# MainBoard_MCU_Power.net
KiCad netlist of a schematic drawn in Altium Designer
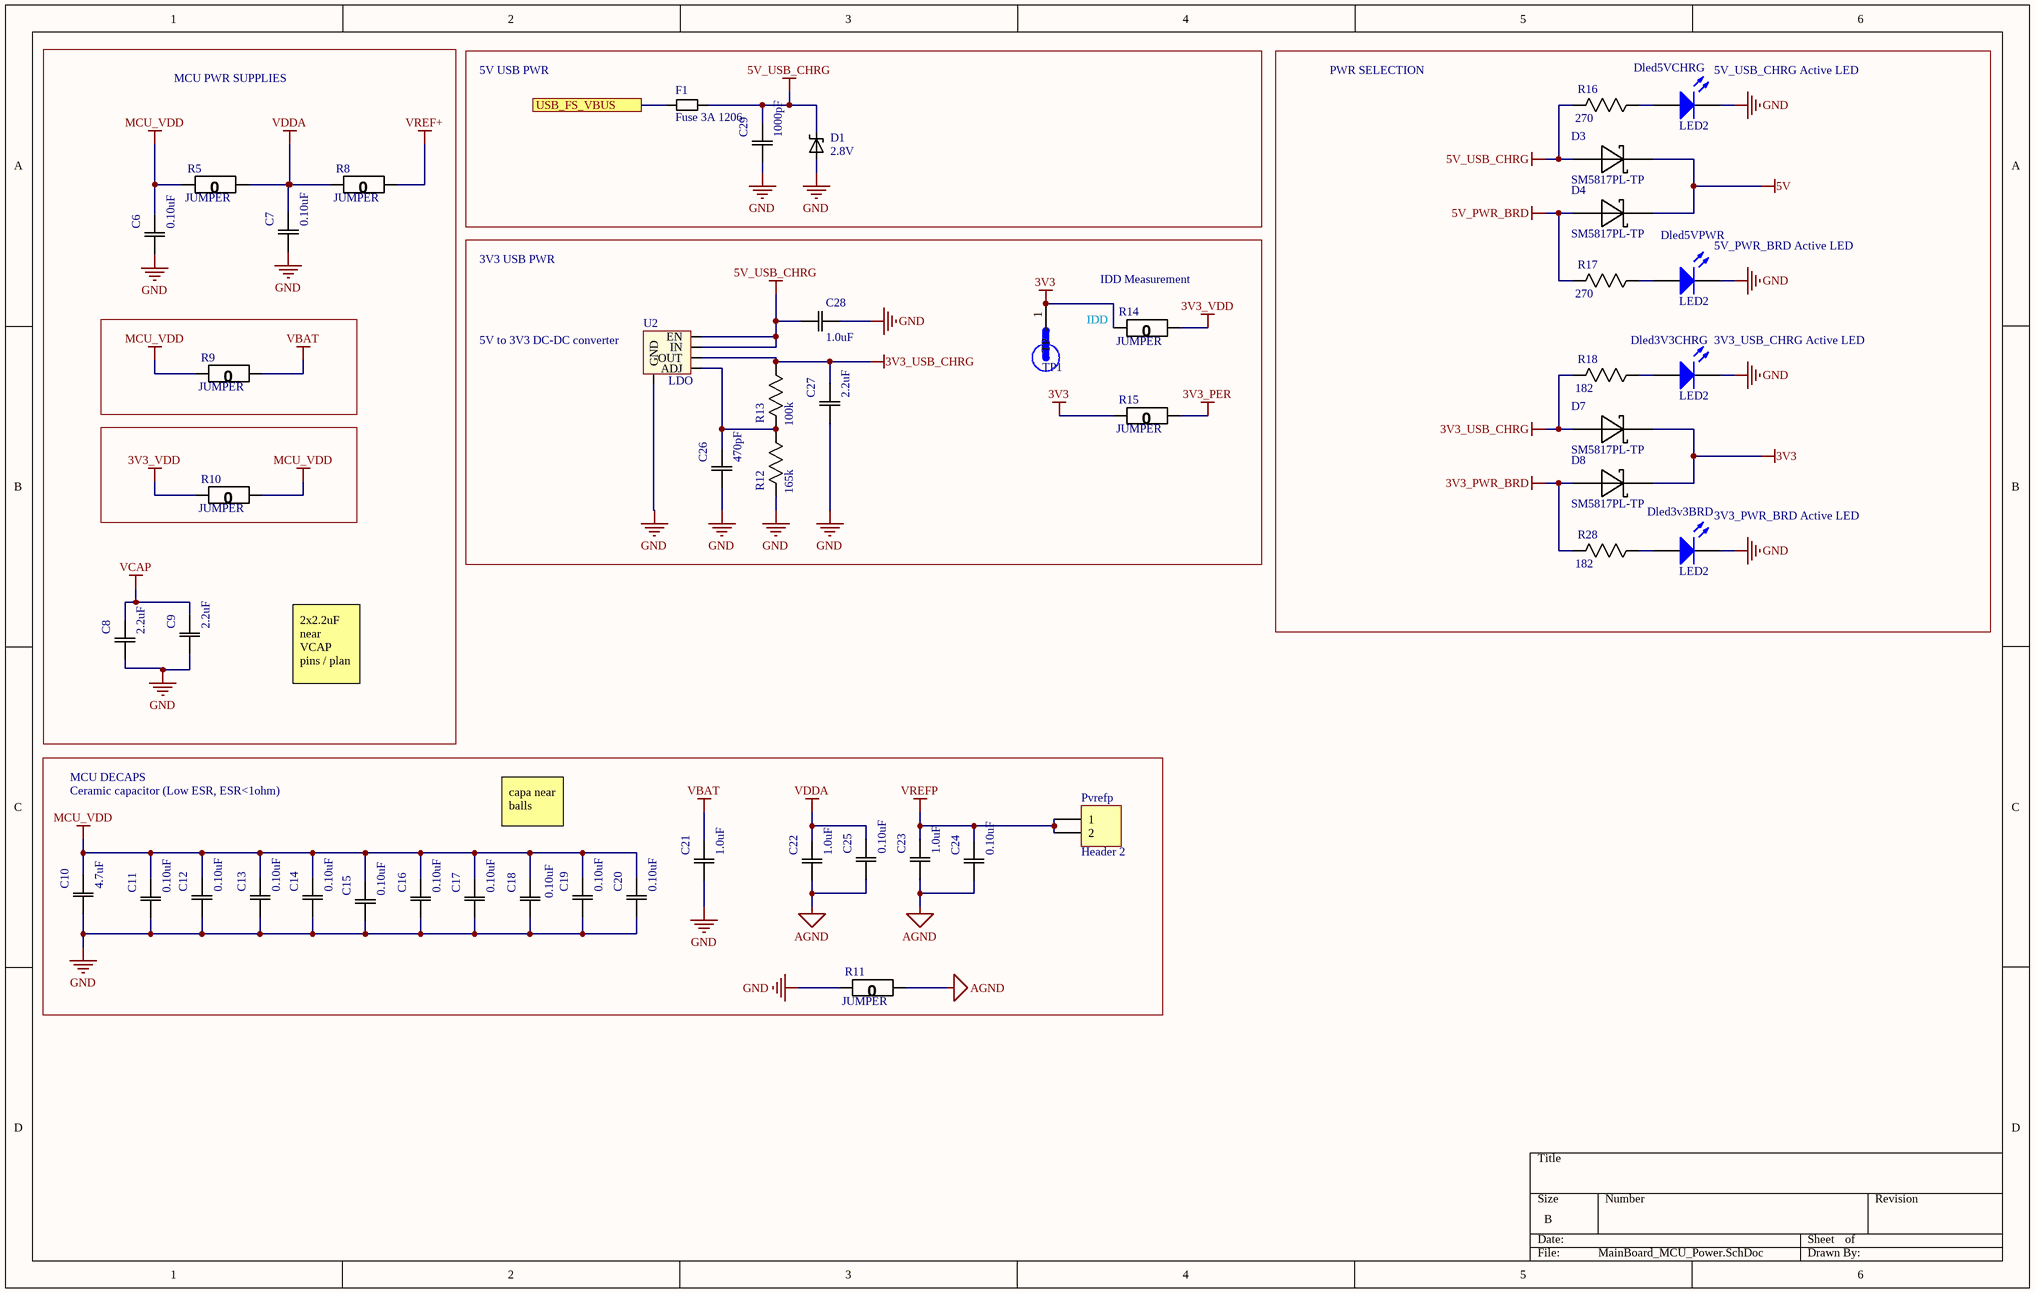
[diagram p0: MainBoard_MCU_Power.SchDoc]

(export (version "E")
  (design (tool "Eeschema 10.0.6"))
  (components
    (comp (ref "C6")
      (value "0.10uF")
      (footprint "0603")
      (description "CAP CER 0.10UF 16V X5R 0603/0805")
      (fields (field (name "TOLERANCE") "10%"))
      (libsource (lib "AltiumLibraries") (part "CAP 0.10uF 16V"))
    )
    (comp (ref "C7")
      (value "0.10uF")
      (footprint "0603")
      (description "CAP CER 0.10UF 16V X5R 0603/0805")
      (fields (field (name "TOLERANCE") "10%"))
      (libsource (lib "AltiumLibraries") (part "CAP 0.10uF 16V"))
    )
    (comp (ref "C8")
      (value "2.2uF")
      (footprint "0603")
      (description "CAP CER 2.2UF 16V X5R 0603/0805")
      (fields (field (name "TOLERANCE") "10%"))
      (libsource (lib "AltiumLibraries") (part "CAP 2.2uF 16V"))
    )
    (comp (ref "C9")
      (value "2.2uF")
      (footprint "0603")
      (description "CAP CER 2.2UF 16V X5R 0603/0805")
      (fields (field (name "TOLERANCE") "10%"))
      (libsource (lib "AltiumLibraries") (part "CAP 2.2uF 16V"))
    )
    (comp (ref "C10")
      (value "4.7uF")
      (footprint "0603")
      (description "CAP CER 4.7UF 16V X5R 0603/0805")
      (fields (field (name "TOLERANCE") "10%"))
      (libsource (lib "AltiumLibraries") (part "CAP 4.7uF 16V"))
    )
    (comp (ref "C11")
      (value "0.10uF")
      (footprint "0603")
      (description "CAP CER 0.10UF 16V X5R 0603/0805")
      (fields (field (name "TOLERANCE") "10%"))
      (libsource (lib "AltiumLibraries") (part "CAP 0.10uF 16V"))
    )
    (comp (ref "C12")
      (value "0.10uF")
      (footprint "0603")
      (description "CAP CER 0.10UF 16V X5R 0603/0805")
      (fields (field (name "TOLERANCE") "10%"))
      (libsource (lib "AltiumLibraries") (part "CAP 0.10uF 16V"))
    )
    (comp (ref "C13")
      (value "0.10uF")
      (footprint "0603")
      (description "CAP CER 0.10UF 16V X5R 0603/0805")
      (fields (field (name "TOLERANCE") "10%"))
      (libsource (lib "AltiumLibraries") (part "CAP 0.10uF 16V"))
    )
    (comp (ref "C14")
      (value "0.10uF")
      (footprint "0603")
      (description "CAP CER 0.10UF 16V X5R 0603/0805")
      (fields (field (name "TOLERANCE") "10%"))
      (libsource (lib "AltiumLibraries") (part "CAP 0.10uF 16V"))
    )
    (comp (ref "C15")
      (value "0.10uF")
      (footprint "0603")
      (description "CAP CER 0.10UF 16V X5R 0603/0805")
      (fields (field (name "TOLERANCE") "10%"))
      (libsource (lib "AltiumLibraries") (part "CAP 0.10uF 16V"))
    )
    (comp (ref "C16")
      (value "0.10uF")
      (footprint "0603")
      (description "CAP CER 0.10UF 16V X5R 0603/0805")
      (fields (field (name "TOLERANCE") "10%"))
      (libsource (lib "AltiumLibraries") (part "CAP 0.10uF 16V"))
    )
    (comp (ref "C17")
      (value "0.10uF")
      (footprint "0603")
      (description "CAP CER 0.10UF 16V X5R 0603/0805")
      (fields (field (name "TOLERANCE") "10%"))
      (libsource (lib "AltiumLibraries") (part "CAP 0.10uF 16V"))
    )
    (comp (ref "C18")
      (value "0.10uF")
      (footprint "0603")
      (description "CAP CER 0.10UF 16V X5R 0603/0805")
      (fields (field (name "TOLERANCE") "10%"))
      (libsource (lib "AltiumLibraries") (part "CAP 0.10uF 16V"))
    )
    (comp (ref "C19")
      (value "0.10uF")
      (footprint "0603")
      (description "CAP CER 0.10UF 16V X5R 0603/0805")
      (fields (field (name "TOLERANCE") "10%"))
      (libsource (lib "AltiumLibraries") (part "CAP 0.10uF 16V"))
    )
    (comp (ref "C20")
      (value "0.10uF")
      (footprint "0603")
      (description "CAP CER 0.10UF 16V X5R 0603/0805")
      (fields (field (name "TOLERANCE") "10%"))
      (libsource (lib "AltiumLibraries") (part "CAP 0.10uF 16V"))
    )
    (comp (ref "C21")
      (value "1.0uF")
      (footprint "0603")
      (description "CAP CER 1.0UF 16V X5R 0603/0805")
      (fields (field (name "TOLERANCE") "10%"))
      (libsource (lib "AltiumLibraries") (part "CAP 1.0uF 16V"))
    )
    (comp (ref "C22")
      (value "1.0uF")
      (footprint "0603")
      (description "CAP CER 1.0UF 16V X5R 0603/0805")
      (fields (field (name "TOLERANCE") "10%"))
      (libsource (lib "AltiumLibraries") (part "CAP 1.0uF 16V"))
    )
    (comp (ref "C23")
      (value "1.0uF")
      (footprint "0603")
      (description "CAP CER 1.0UF 16V X5R 0603/0805")
      (fields (field (name "TOLERANCE") "10%"))
      (libsource (lib "AltiumLibraries") (part "CAP 1.0uF 16V"))
    )
    (comp (ref "C24")
      (value "0.10uF")
      (footprint "0603")
      (description "CAP CER 0.10UF 16V X5R 0603/0805")
      (fields (field (name "TOLERANCE") "10%"))
      (libsource (lib "AltiumLibraries") (part "CAP 0.10uF 16V"))
    )
    (comp (ref "C25")
      (value "0.10uF")
      (footprint "0603")
      (description "CAP CER 0.10UF 16V X5R 0603/0805")
      (fields (field (name "TOLERANCE") "10%"))
      (libsource (lib "AltiumLibraries") (part "CAP 0.10uF 16V"))
    )
    (comp (ref "C26")
      (value "470pF")
      (footprint "0603")
      (description "CAP CER 470PF 16V X5R 0603/0805")
      (fields (field (name "TOLERANCE") "10%"))
      (libsource (lib "AltiumLibraries") (part "CAP 470pF 16V"))
    )
    (comp (ref "C27")
      (value "2.2uF")
      (footprint "0603")
      (description "CAP CER 2.2UF 16V X5R 0603/0805")
      (fields (field (name "TOLERANCE") "10%"))
      (libsource (lib "") (part "CAP 2.2uF 16V_1"))
    )
    (comp (ref "C28")
      (value "1.0uF")
      (footprint "0603")
      (description "CAP CER 1.0UF 16V X5R 0603/0805")
      (fields (field (name "TOLERANCE") "10%"))
      (libsource (lib "AltiumLibraries") (part "CAP 1.0uF 16V"))
    )
    (comp (ref "C29")
      (value "1000pF")
      (footprint "0603")
      (description "CAP CER 1000PF 16V X5R 0603/0805")
      (fields (field (name "TOLERANCE") "10%"))
      (libsource (lib "AltiumLibraries") (part "CAP 1000pF 16V"))
    )
    (comp (ref "D1")
      (value "2.8V")
      (footprint "SOD-123")
      (description "Zener Diode 2.8V 500mW ±5% Surface Mount SOD-123")
      (libsource (lib "AltiumLibraries") (part "DIODE ZENER 2.8V 500mW"))
    )
    (comp (ref "D3")
      (value "SM5817PL-TP")
      (footprint "SOD-123")
      (description "Diode Schottky 20V 1A Surface Mount SOD-123FL")
      (fields (field (name "MF") "Micro Commercial Co"))
      (libsource (lib "AltiumLibraries") (part "DIODE SCHOTTKY 20V 1A"))
    )
    (comp (ref "D4")
      (value "SM5817PL-TP")
      (footprint "SOD-123")
      (description "Diode Schottky 20V 1A Surface Mount SOD-123FL")
      (fields (field (name "MF") "Micro Commercial Co"))
      (libsource (lib "AltiumLibraries") (part "DIODE SCHOTTKY 20V 1A"))
    )
    (comp (ref "D7")
      (value "SM5817PL-TP")
      (footprint "SOD-123")
      (description "Diode Schottky 20V 1A Surface Mount SOD-123FL")
      (fields (field (name "MF") "Micro Commercial Co"))
      (libsource (lib "AltiumLibraries") (part "DIODE SCHOTTKY 20V 1A"))
    )
    (comp (ref "D8")
      (value "SM5817PL-TP")
      (footprint "SOD-123")
      (description "Diode Schottky 20V 1A Surface Mount SOD-123FL")
      (fields (field (name "MF") "Micro Commercial Co"))
      (libsource (lib "AltiumLibraries") (part "DIODE SCHOTTKY 20V 1A"))
    )
    (comp (ref "Dled3v3BRD")
      (value "LED2")
      (footprint "3.2X1.6X1.1")
      (description "Typical RED, GREEN, YELLOW, AMBER GaAs LED")
      (libsource (lib "AltiumLibraries") (part "LED GREEN SMD"))
    )
    (comp (ref "Dled3V3CHRG")
      (value "LED2")
      (footprint "3.2X1.6X1.1")
      (description "Typical RED, GREEN, YELLOW, AMBER GaAs LED")
      (libsource (lib "AltiumLibraries") (part "LED GREEN SMD"))
    )
    (comp (ref "Dled5VCHRG")
      (value "LED2")
      (footprint "3.2X1.6X1.1")
      (description "Typical RED, GREEN, YELLOW, AMBER GaAs LED")
      (libsource (lib "AltiumLibraries") (part "LED GREEN SMD"))
    )
    (comp (ref "Dled5VPWR")
      (value "LED2")
      (footprint "3.2X1.6X1.1")
      (description "Typical RED, GREEN, YELLOW, AMBER GaAs LED")
      (libsource (lib "AltiumLibraries") (part "LED GREEN SMD"))
    )
    (comp (ref "F1")
      (value "Fuse 3A 1206")
      (footprint "1206")
      (description "FUSE 3A 63V AC/DC SLOW 1206")
      (libsource (lib "AltiumLibraries") (part "FUSE 3A 63V SLOW"))
    )
    (comp (ref "Pvrefp")
      (value "Header 2")
      (footprint "HDR1X2")
      (description "Header, 2-Pin")
      (fields (field (name "PUBLISHER") "Altium Limited"))
      (libsource (lib "Miscellaneous Connectors") (part "Header 2"))
    )
    (comp (ref "R5")
      (value "JUMPER")
      (footprint "0805")
      (description "RES SMD 0 OHM JUMPER GENERIC 0805")
      (libsource (lib "AltiumLibraries") (part "RES 0 JUMPER"))
    )
    (comp (ref "R8")
      (value "JUMPER")
      (footprint "0805")
      (description "RES SMD 0 OHM JUMPER GENERIC 0805")
      (libsource (lib "AltiumLibraries") (part "RES 0 JUMPER"))
    )
    (comp (ref "R9")
      (value "JUMPER")
      (footprint "0805")
      (description "RES SMD 0 OHM JUMPER GENERIC 0805")
      (libsource (lib "AltiumLibraries") (part "RES 0 JUMPER"))
    )
    (comp (ref "R10")
      (value "JUMPER")
      (footprint "0805")
      (description "RES SMD 0 OHM JUMPER GENERIC 0805")
      (libsource (lib "AltiumLibraries") (part "RES 0 JUMPER"))
    )
    (comp (ref "R11")
      (value "JUMPER")
      (footprint "0805")
      (description "RES SMD 0 OHM JUMPER GENERIC 0805")
      (libsource (lib "AltiumLibraries") (part "RES 0 JUMPER"))
    )
    (comp (ref "R12")
      (value "165k")
      (footprint "0805")
      (description "RES SMD 165K OHM 1% 1/4W 0805")
      (fields (field (name "TOLERANCE") "1%"))
      (libsource (lib "AltiumLibraries") (part "RES 165k 1/4W"))
    )
    (comp (ref "R13")
      (value "100k")
      (footprint "0805")
      (description "RES SMD 100K OHM 1% 1/8W 0805")
      (fields (field (name "TOLERANCE") "1%"))
      (libsource (lib "AltiumLibraries") (part "RES 100k 1/8W - 1%"))
    )
    (comp (ref "R14")
      (value "JUMPER")
      (footprint "0805")
      (description "RES SMD 0 OHM JUMPER GENERIC 0805")
      (libsource (lib "AltiumLibraries") (part "RES 0 JUMPER"))
    )
    (comp (ref "R15")
      (value "JUMPER")
      (footprint "0805")
      (description "RES SMD 0 OHM JUMPER GENERIC 0805")
      (libsource (lib "AltiumLibraries") (part "RES 0 JUMPER"))
    )
    (comp (ref "R16")
      (value "270")
      (footprint "0805")
      (description "RES SMD 270 OHM 5% 1/8W 0805")
      (fields (field (name "TOLERANCE") "5%"))
      (libsource (lib "AltiumLibraries") (part "RES 270.0 1/8W"))
    )
    (comp (ref "R17")
      (value "270")
      (footprint "0805")
      (description "RES SMD 270 OHM 5% 1/8W 0805")
      (fields (field (name "TOLERANCE") "5%"))
      (libsource (lib "AltiumLibraries") (part "RES 270.0 1/8W"))
    )
    (comp (ref "R18")
      (value "182")
      (footprint "0805")
      (description "RES SMD 182 OHM 1% 1/8W 0805")
      (fields (field (name "TOLERANCE") "1%"))
      (libsource (lib "AltiumLibraries") (part "RES 182.0 1/8W"))
    )
    (comp (ref "R28")
      (value "182")
      (footprint "0805")
      (description "RES SMD 182 OHM 1% 1/8W 0805")
      (fields (field (name "TOLERANCE") "1%"))
      (libsource (lib "AltiumLibraries") (part "RES 182.0 1/8W"))
    )
    (comp (ref "TP1")
      (value "Test Point - 5019")
      (footprint "TP380X203")
      (description "PC Test Point, Miniature Phosphor Bronze, Silver Plating Surface Mount Mounting Type")
      (fields (field (name "MP") "5019") (field (name "MF") "Keystone Electronics"))
      (libsource (lib "AltiumLibraries") (part "Test Point - 5019"))
    )
    (comp (ref "U2")
      (value "LDO")
      (footprint "REG LIN POS ADJ 500MA 8SOIC")
      (description "Linear Voltage Regulator IC  1 Output  500mA 8-SOIC")
      (fields (field (name "MF") "Texas Instruments") (field (name "MP") "TL5209DR"))
      (libsource (lib "AltiumLibraries") (part "REG LIN POS ADJ"))
    )
  )
  (nets
    (net (code "1") (name "/USB_FS_VBUS") (class "Default")
      (node (ref "F1") (pin "1") (pinfunction "1_1") (pintype "passive"))
    )
    (net (code "2") (name "3V3") (class "Default")
      (node (ref "D7") (pin "C") (pinfunction "K_C") (pintype "passive"))
      (node (ref "D8") (pin "C") (pinfunction "K_C") (pintype "passive"))
      (node (ref "R14") (pin "2") (pinfunction "R2_2") (pintype "passive"))
      (node (ref "R15") (pin "2") (pinfunction "R2_2") (pintype "passive"))
      (node (ref "TP1") (pin "1") (pinfunction "TP_1") (pintype "passive"))
    )
    (net (code "3") (name "3V3_PER") (class "Default")
      (node (ref "R15") (pin "1") (pinfunction "R1_1") (pintype "passive"))
    )
    (net (code "4") (name "3V3_PWR_BRD") (class "Default")
      (node (ref "D8") (pin "A") (pinfunction "A_A") (pintype "passive"))
      (node (ref "R28") (pin "2") (pinfunction "R2_2") (pintype "passive"))
    )
    (net (code "5") (name "3V3_USB_CHRG") (class "Default")
      (node (ref "C27") (pin "2") (pinfunction "C2_2") (pintype "passive"))
      (node (ref "D7") (pin "A") (pinfunction "A_A") (pintype "passive"))
      (node (ref "R13") (pin "1") (pinfunction "R1_1") (pintype "passive"))
      (node (ref "R18") (pin "2") (pinfunction "R2_2") (pintype "passive"))
      (node (ref "U2") (pin "OUT") (pinfunction "OUT_OUT") (pintype "passive"))
    )
    (net (code "6") (name "3V3_VDD") (class "Default")
      (node (ref "R10") (pin "2") (pinfunction "R2_2") (pintype "passive"))
      (node (ref "R14") (pin "1") (pinfunction "R1_1") (pintype "passive"))
    )
    (net (code "7") (name "5V") (class "Default")
      (node (ref "D3") (pin "C") (pinfunction "K_C") (pintype "passive"))
      (node (ref "D4") (pin "C") (pinfunction "K_C") (pintype "passive"))
    )
    (net (code "8") (name "5V_PWR_BRD") (class "Default")
      (node (ref "D4") (pin "A") (pinfunction "A_A") (pintype "passive"))
      (node (ref "R17") (pin "2") (pinfunction "R2_2") (pintype "passive"))
    )
    (net (code "9") (name "5V_USB_CHRG") (class "Default")
      (node (ref "C28") (pin "1") (pinfunction "C1_1") (pintype "passive"))
      (node (ref "C29") (pin "2") (pinfunction "C2_2") (pintype "passive"))
      (node (ref "D1") (pin "C") (pinfunction "C_C") (pintype "passive"))
      (node (ref "D3") (pin "A") (pinfunction "A_A") (pintype "passive"))
      (node (ref "F1") (pin "2") (pinfunction "2_2") (pintype "passive"))
      (node (ref "R16") (pin "2") (pinfunction "R2_2") (pintype "passive"))
      (node (ref "U2") (pin "EN") (pinfunction "EN_EN") (pintype "passive"))
      (node (ref "U2") (pin "IN") (pinfunction "IN_IN") (pintype "passive"))
    )
    (net (code "10") (name "AGND") (class "Default")
      (node (ref "C22") (pin "1") (pinfunction "C1_1") (pintype "passive"))
      (node (ref "C23") (pin "1") (pinfunction "C1_1") (pintype "passive"))
      (node (ref "C24") (pin "1") (pinfunction "C1_1") (pintype "passive"))
      (node (ref "C25") (pin "1") (pinfunction "C1_1") (pintype "passive"))
      (node (ref "R11") (pin "1") (pinfunction "R1_1") (pintype "passive"))
    )
    (net (code "11") (name "GND") (class "Default")
      (node (ref "C10") (pin "1") (pinfunction "C1_1") (pintype "passive"))
      (node (ref "C11") (pin "1") (pinfunction "C1_1") (pintype "passive"))
      (node (ref "C12") (pin "1") (pinfunction "C1_1") (pintype "passive"))
      (node (ref "C13") (pin "1") (pinfunction "C1_1") (pintype "passive"))
      (node (ref "C14") (pin "1") (pinfunction "C1_1") (pintype "passive"))
      (node (ref "C15") (pin "1") (pinfunction "C1_1") (pintype "passive"))
      (node (ref "C16") (pin "1") (pinfunction "C1_1") (pintype "passive"))
      (node (ref "C17") (pin "1") (pinfunction "C1_1") (pintype "passive"))
      (node (ref "C18") (pin "1") (pinfunction "C1_1") (pintype "passive"))
      (node (ref "C19") (pin "1") (pinfunction "C1_1") (pintype "passive"))
      (node (ref "C20") (pin "1") (pinfunction "C1_1") (pintype "passive"))
      (node (ref "C21") (pin "1") (pinfunction "C1_1") (pintype "passive"))
      (node (ref "C26") (pin "1") (pinfunction "C1_1") (pintype "passive"))
      (node (ref "C27") (pin "1") (pinfunction "C1_1") (pintype "passive"))
      (node (ref "C28") (pin "2") (pinfunction "C2_2") (pintype "passive"))
      (node (ref "C29") (pin "1") (pinfunction "C1_1") (pintype "passive"))
      (node (ref "C6") (pin "1") (pinfunction "C1_1") (pintype "passive"))
      (node (ref "C7") (pin "1") (pinfunction "C1_1") (pintype "passive"))
      (node (ref "C8") (pin "1") (pinfunction "C1_1") (pintype "passive"))
      (node (ref "C9") (pin "1") (pinfunction "C1_1") (pintype "passive"))
      (node (ref "D1") (pin "A") (pinfunction "A_A") (pintype "passive"))
      (node (ref "Dled3V3CHRG") (pin "2") (pinfunction "K_2") (pintype "passive"))
      (node (ref "Dled3v3BRD") (pin "2") (pinfunction "K_2") (pintype "passive"))
      (node (ref "Dled5VCHRG") (pin "2") (pinfunction "K_2") (pintype "passive"))
      (node (ref "Dled5VPWR") (pin "2") (pinfunction "K_2") (pintype "passive"))
      (node (ref "R11") (pin "2") (pinfunction "R2_2") (pintype "passive"))
      (node (ref "R12") (pin "2") (pinfunction "R2_2") (pintype "passive"))
      (node (ref "U2") (pin "GND") (pinfunction "GND_GND") (pintype "passive"))
    )
    (net (code "12") (name "MCU_VDD") (class "Default")
      (node (ref "C10") (pin "2") (pinfunction "C2_2") (pintype "passive"))
      (node (ref "C11") (pin "2") (pinfunction "C2_2") (pintype "passive"))
      (node (ref "C12") (pin "2") (pinfunction "C2_2") (pintype "passive"))
      (node (ref "C13") (pin "2") (pinfunction "C2_2") (pintype "passive"))
      (node (ref "C14") (pin "2") (pinfunction "C2_2") (pintype "passive"))
      (node (ref "C15") (pin "2") (pinfunction "C2_2") (pintype "passive"))
      (node (ref "C16") (pin "2") (pinfunction "C2_2") (pintype "passive"))
      (node (ref "C17") (pin "2") (pinfunction "C2_2") (pintype "passive"))
      (node (ref "C18") (pin "2") (pinfunction "C2_2") (pintype "passive"))
      (node (ref "C19") (pin "2") (pinfunction "C2_2") (pintype "passive"))
      (node (ref "C20") (pin "2") (pinfunction "C2_2") (pintype "passive"))
      (node (ref "C6") (pin "2") (pinfunction "C2_2") (pintype "passive"))
      (node (ref "R10") (pin "1") (pinfunction "R1_1") (pintype "passive"))
      (node (ref "R5") (pin "2") (pinfunction "R2_2") (pintype "passive"))
      (node (ref "R9") (pin "2") (pinfunction "R2_2") (pintype "passive"))
    )
    (net (code "13") (name "Net-(C26-C2)") (class "Default")
      (node (ref "C26") (pin "2") (pinfunction "C2_2") (pintype "passive"))
      (node (ref "R12") (pin "1") (pinfunction "R1_1") (pintype "passive"))
      (node (ref "R13") (pin "2") (pinfunction "R2_2") (pintype "passive"))
      (node (ref "U2") (pin "ADJ") (pinfunction "ADJ_ADJ") (pintype "passive"))
    )
    (net (code "14") (name "Net-(Dled3V3CHRG-A)") (class "Default")
      (node (ref "Dled3V3CHRG") (pin "1") (pinfunction "A_1") (pintype "passive"))
      (node (ref "R18") (pin "1") (pinfunction "R1_1") (pintype "passive"))
    )
    (net (code "15") (name "Net-(Dled3v3BRD-A)") (class "Default")
      (node (ref "Dled3v3BRD") (pin "1") (pinfunction "A_1") (pintype "passive"))
      (node (ref "R28") (pin "1") (pinfunction "R1_1") (pintype "passive"))
    )
    (net (code "16") (name "Net-(Dled5VCHRG-A)") (class "Default")
      (node (ref "Dled5VCHRG") (pin "1") (pinfunction "A_1") (pintype "passive"))
      (node (ref "R16") (pin "1") (pinfunction "R1_1") (pintype "passive"))
    )
    (net (code "17") (name "Net-(Dled5VPWR-A)") (class "Default")
      (node (ref "Dled5VPWR") (pin "1") (pinfunction "A_1") (pintype "passive"))
      (node (ref "R17") (pin "1") (pinfunction "R1_1") (pintype "passive"))
    )
    (net (code "18") (name "VBAT") (class "Default")
      (node (ref "C21") (pin "2") (pinfunction "C2_2") (pintype "passive"))
      (node (ref "R9") (pin "1") (pinfunction "R1_1") (pintype "passive"))
    )
    (net (code "19") (name "VCAP") (class "Default")
      (node (ref "C8") (pin "2") (pinfunction "C2_2") (pintype "passive"))
      (node (ref "C9") (pin "2") (pinfunction "C2_2") (pintype "passive"))
    )
    (net (code "20") (name "VDDA") (class "Default")
      (node (ref "C22") (pin "2") (pinfunction "C2_2") (pintype "passive"))
      (node (ref "C25") (pin "2") (pinfunction "C2_2") (pintype "passive"))
      (node (ref "C7") (pin "2") (pinfunction "C2_2") (pintype "passive"))
      (node (ref "R5") (pin "1") (pinfunction "R1_1") (pintype "passive"))
      (node (ref "R8") (pin "2") (pinfunction "R2_2") (pintype "passive"))
    )
    (net (code "21") (name "VREF+") (class "Default")
      (node (ref "R8") (pin "1") (pinfunction "R1_1") (pintype "passive"))
    )
    (net (code "22") (name "VREFP") (class "Default")
      (node (ref "C23") (pin "2") (pinfunction "C2_2") (pintype "passive"))
      (node (ref "C24") (pin "2") (pinfunction "C2_2") (pintype "passive"))
      (node (ref "Pvrefp") (pin "1") (pinfunction "1_1") (pintype "passive"))
      (node (ref "Pvrefp") (pin "2") (pinfunction "2_2") (pintype "passive"))
    )
  )
)
